# pOWER.net
KiCad netlist of a schematic drawn in Altium Designer
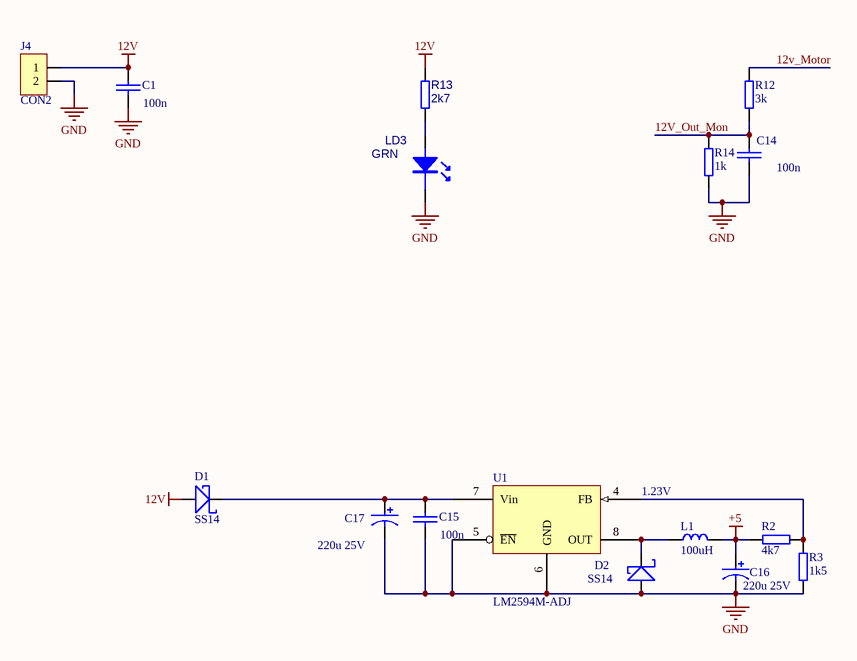
[diagram p0: pOWER.SchDoc]

(export (version "E")
  (design (tool "Eeschema 10.0.6"))
  (components
    (comp (ref "C1") (value "100n") (footprint "0603") (libsource (lib "DEVICE") (part "CAP")))
    (comp (ref "C14") (value "100n") (footprint "0603") (libsource (lib "D_LINEAR") (part "CAP")))
    (comp (ref "C15") (value "100n") (footprint "0603") (libsource (lib "DEVICE") (part "CAP")))
    (comp (ref "C16")
      (value "220u 25V")
      (footprint "RB.15/.32")
      (libsource (lib "*") (part "CAPACITOR POL-S"))
    )
    (comp (ref "C17")
      (value "220u 25V")
      (footprint "RB.15/.32")
      (libsource (lib "DEVICE") (part "CAPACITOR POL-S"))
    )
    (comp (ref "D1")
      (value "SS14")
      (footprint "DO-214AC")
      (libsource (lib "DEVICE") (part "DIODE SCHOTTKY-S"))
    )
    (comp (ref "D2")
      (value "SS14")
      (footprint "DO-214AC")
      (libsource (lib "DEVICE") (part "DIODE SCHOTTKY-S"))
    )
    (comp (ref "J4") (value "CON2") (footprint "WEID2R") (libsource (lib "DEVICE") (part "CON2")))
    (comp (ref "L1") (value "100uH") (footprint "INDUCTOR6B") (libsource (lib "*") (part "INDUCTOR6")))
    (comp (ref "LD3") (value "GRN") (footprint "0805DIODE") (libsource (lib "*") (part "LED")))
    (comp (ref "R2") (value "4k7") (footprint "0603") (libsource (lib "DEVICE") (part "RES-AX0.3")))
    (comp (ref "R3") (value "1k5") (footprint "0603") (libsource (lib "DEVICE") (part "RES-AX0.3")))
    (comp (ref "R12") (value "3k") (footprint "0603") (libsource (lib "DEVICE") (part "RES8")))
    (comp (ref "R13") (value "2k7") (footprint "0603") (libsource (lib "DEVICE") (part "RES8")))
    (comp (ref "R14") (value "1k") (footprint "0603") (libsource (lib "DEVICE") (part "RES8")))
    (comp (ref "U1") (value "LM2594M-ADJ") (footprint "M08A_N") (libsource (lib "NS-EXTRA") (part "LM2594")))
  )
  (nets
    (net (code "1") (name "+5") (class "Default")
      (node (ref "C16") (pin "1") (pinfunction "1_1") (pintype "passive"))
      (node (ref "L1") (pin "2") (pintype "passive"))
      (node (ref "R2") (pin "2") (pintype "passive"))
    )
    (net (code "2") (name "/12V_Out_Mon") (class "Default")
      (node (ref "C14") (pin "2") (pintype "passive"))
      (node (ref "R12") (pin "1") (pintype "passive"))
      (node (ref "R14") (pin "2") (pintype "passive"))
    )
    (net (code "3") (name "/12v_Motor") (class "Default") (node (ref "R12") (pin "2") (pintype "passive")))
    (net (code "4") (name "12V") (class "Default")
      (node (ref "C1") (pin "2") (pintype "passive"))
      (node (ref "D1") (pin "A") (pinfunction "A_A") (pintype "passive"))
      (node (ref "J4") (pin "1") (pinfunction "1_1") (pintype "passive"))
      (node (ref "R13") (pin "1") (pintype "passive"))
    )
    (net (code "5") (name "GND") (class "Default")
      (node (ref "C1") (pin "1") (pintype "passive"))
      (node (ref "C14") (pin "1") (pintype "passive"))
      (node (ref "C15") (pin "1") (pintype "passive"))
      (node (ref "C16") (pin "2") (pinfunction "2_2") (pintype "passive"))
      (node (ref "C17") (pin "2") (pinfunction "2_2") (pintype "passive"))
      (node (ref "D2") (pin "A") (pinfunction "A_A") (pintype "passive"))
      (node (ref "J4") (pin "2") (pinfunction "2_2") (pintype "passive"))
      (node (ref "LD3") (pin "K") (pintype "passive"))
      (node (ref "R14") (pin "1") (pintype "passive"))
      (node (ref "R3") (pin "1") (pintype "passive"))
      (node (ref "U1") (pin "5") (pinfunction "~{EN}_5") (pintype "passive"))
      (node (ref "U1") (pin "6") (pinfunction "GND_6") (pintype "power_in"))
    )
    (net (code "6") (name "Net-(LD3-PadA)") (class "Default")
      (node (ref "LD3") (pin "A") (pintype "passive"))
      (node (ref "R13") (pin "2") (pintype "passive"))
    )
    (net (code "7") (name "Net-(U1-FB)") (class "Default")
      (node (ref "R2") (pin "1") (pintype "passive"))
      (node (ref "R3") (pin "2") (pintype "passive"))
      (node (ref "U1") (pin "4") (pinfunction "FB_4") (pintype "input"))
    )
    (net (code "8") (name "Net-(U1-OUT)") (class "Default")
      (node (ref "D2") (pin "K") (pinfunction "K_K") (pintype "passive"))
      (node (ref "L1") (pin "1") (pintype "passive"))
      (node (ref "U1") (pin "8") (pinfunction "OUT_8") (pintype "power_in"))
    )
    (net (code "9") (name "Net-(U1-Vin)") (class "Default")
      (node (ref "C15") (pin "2") (pintype "passive"))
      (node (ref "C17") (pin "1") (pinfunction "1_1") (pintype "passive"))
      (node (ref "D1") (pin "K") (pinfunction "K_K") (pintype "passive"))
      (node (ref "U1") (pin "7") (pinfunction "Vin_7") (pintype "passive"))
    )
  )
)
